# PWR_board_CHM.net
KiCad netlist of a schematic drawn in Altium Designer
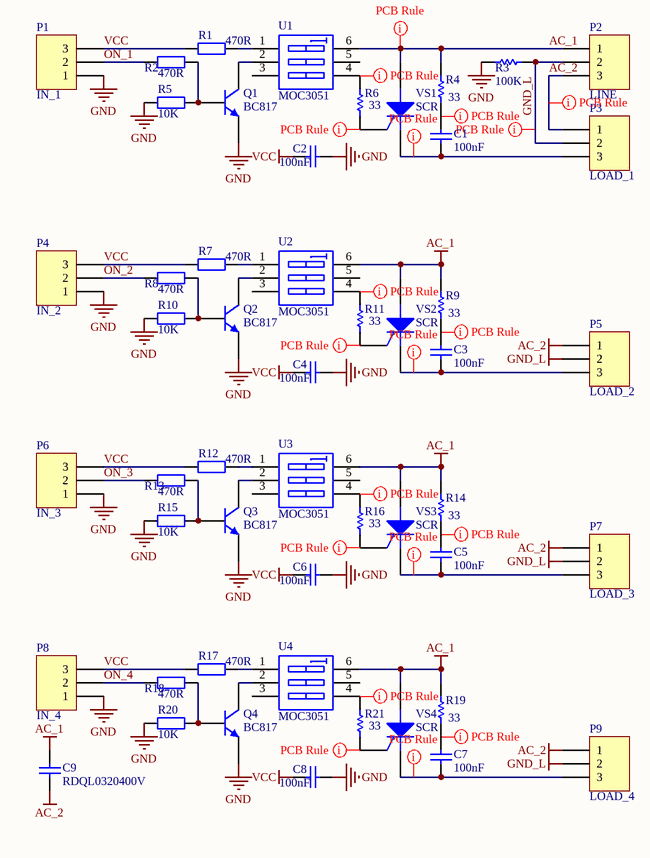
[diagram p0: PWR board_CHM.SchDoc]

(export (version "E")
  (design (tool "Eeschema 10.0.6"))
  (components
    (comp (ref "C1")
      (value "100nF")
      (footprint "AXIAL-0.7")
      (description "Ceramic High Voltage Disc Capacitor, Class 2: 2200pF 6kV K 2000")
      (fields (field (name "PUBLISHER") "Altium Limited"))
      (libsource (lib "Vishay Draloric Ceramic Disc Capacitor") (part "HFZ222MBFEJ0K"))
    )
    (comp (ref "C2")
      (value "100nF")
      (footprint "0805")
      (description "Ceramic Chip Capacitor - Standard")
      (fields (field (name "Comment") "C0805") (field (name "PUBLISHER") "Altium Limited"))
      (libsource (lib "KEMET Chip Capacitor") (part "C0805"))
    )
    (comp (ref "C3")
      (value "100nF")
      (footprint "AXIAL-0.7")
      (description "Ceramic High Voltage Disc Capacitor, Class 2: 2200pF 6kV K 2000")
      (fields (field (name "PUBLISHER") "Altium Limited"))
      (libsource (lib "Vishay Draloric Ceramic Disc Capacitor") (part "HFZ222MBFEJ0K"))
    )
    (comp (ref "C4")
      (value "100nF")
      (footprint "0805")
      (description "Ceramic Chip Capacitor - Standard")
      (fields (field (name "Comment") "C0805") (field (name "PUBLISHER") "Altium Limited"))
      (libsource (lib "KEMET Chip Capacitor") (part "C0805"))
    )
    (comp (ref "C5")
      (value "100nF")
      (footprint "AXIAL-0.7")
      (description "Ceramic High Voltage Disc Capacitor, Class 2: 2200pF 6kV K 2000")
      (fields (field (name "PUBLISHER") "Altium Limited"))
      (libsource (lib "Vishay Draloric Ceramic Disc Capacitor") (part "HFZ222MBFEJ0K"))
    )
    (comp (ref "C6")
      (value "100nF")
      (footprint "0805")
      (description "Ceramic Chip Capacitor - Standard")
      (fields (field (name "Comment") "C0805") (field (name "PUBLISHER") "Altium Limited"))
      (libsource (lib "KEMET Chip Capacitor") (part "C0805"))
    )
    (comp (ref "C7")
      (value "100nF")
      (footprint "AXIAL-0.7")
      (description "Ceramic High Voltage Disc Capacitor, Class 2: 2200pF 6kV K 2000")
      (fields (field (name "PUBLISHER") "Altium Limited"))
      (libsource (lib "Vishay Draloric Ceramic Disc Capacitor") (part "HFZ222MBFEJ0K"))
    )
    (comp (ref "C8")
      (value "100nF")
      (footprint "0805")
      (description "Ceramic Chip Capacitor - Standard")
      (fields (field (name "Comment") "C0805") (field (name "PUBLISHER") "Altium Limited"))
      (libsource (lib "KEMET Chip Capacitor") (part "C0805"))
    )
    (comp (ref "C9")
      (value "RDQL0320400V")
      (footprint "AXIAL-0.7")
      (fields (field (name "PUBLISHER") "Altium Limited"))
      (libsource (lib "Vishay Draloric Ceramic Tubular Capacitor") (part "RDQL0320400V"))
    )
    (comp (ref "P1")
      (value "IN_1")
      (footprint "DG390-5.0-03P")
      (description "Header, 3-Pin")
      (fields (field (name "PUBLISHER") "Altium Limited"))
      (libsource (lib "") (part "Header 3_1"))
    )
    (comp (ref "P2")
      (value "LINE")
      (footprint "DG390-5.0-03P")
      (description "Header, 3-Pin")
      (fields (field (name "PUBLISHER") "Altium Limited"))
      (libsource (lib "Miscellaneous Connectors") (part "Header 3"))
    )
    (comp (ref "P3")
      (value "LOAD_1")
      (footprint "DG390-5.0-03P")
      (description "Header, 3-Pin")
      (fields (field (name "PUBLISHER") "Altium Limited"))
      (libsource (lib "Miscellaneous Connectors") (part "Header 3"))
    )
    (comp (ref "P4")
      (value "IN_2")
      (footprint "DG390-5.0-03P")
      (description "Header, 3-Pin")
      (fields (field (name "PUBLISHER") "Altium Limited"))
      (libsource (lib "") (part "Header 3_1"))
    )
    (comp (ref "P5")
      (value "LOAD_2")
      (footprint "DG390-5.0-03P")
      (description "Header, 3-Pin")
      (fields (field (name "PUBLISHER") "Altium Limited"))
      (libsource (lib "Miscellaneous Connectors") (part "Header 3"))
    )
    (comp (ref "P6")
      (value "IN_3")
      (footprint "DG390-5.0-03P")
      (description "Header, 3-Pin")
      (fields (field (name "PUBLISHER") "Altium Limited"))
      (libsource (lib "") (part "Header 3_1"))
    )
    (comp (ref "P7")
      (value "LOAD_3")
      (footprint "DG390-5.0-03P")
      (description "Header, 3-Pin")
      (fields (field (name "PUBLISHER") "Altium Limited"))
      (libsource (lib "Miscellaneous Connectors") (part "Header 3"))
    )
    (comp (ref "P8")
      (value "IN_4")
      (footprint "DG390-5.0-03P")
      (description "Header, 3-Pin")
      (fields (field (name "PUBLISHER") "Altium Limited"))
      (libsource (lib "") (part "Header 3_1"))
    )
    (comp (ref "P9")
      (value "LOAD_4")
      (footprint "DG390-5.0-03P")
      (description "Header, 3-Pin")
      (fields (field (name "PUBLISHER") "Altium Limited"))
      (libsource (lib "Miscellaneous Connectors") (part "Header 3"))
    )
    (comp (ref "Q1")
      (value "BC817")
      (footprint "SOT23_M")
      (description "NPN Bipolar Transistor")
      (fields (field (name "PUBLISHER") "Altium Limited"))
      (libsource (lib "Miscellaneous Devices") (part "QNPN"))
    )
    (comp (ref "Q2")
      (value "BC817")
      (footprint "SOT23_M")
      (description "NPN Bipolar Transistor")
      (fields (field (name "PUBLISHER") "Altium Limited"))
      (libsource (lib "Miscellaneous Devices") (part "QNPN"))
    )
    (comp (ref "Q3")
      (value "BC817")
      (footprint "SOT23_M")
      (description "NPN Bipolar Transistor")
      (fields (field (name "PUBLISHER") "Altium Limited"))
      (libsource (lib "Miscellaneous Devices") (part "QNPN"))
    )
    (comp (ref "Q4")
      (value "BC817")
      (footprint "SOT23_M")
      (description "NPN Bipolar Transistor")
      (fields (field (name "PUBLISHER") "Altium Limited"))
      (libsource (lib "Miscellaneous Devices") (part "QNPN"))
    )
    (comp (ref "R1")
      (value "470R")
      (footprint "6-0805_N")
      (description "Resistor")
      (fields (field (name "Comment") "Res2") (field (name "PUBLISHER") "Altium Limited"))
      (libsource (lib "Miscellaneous Devices") (part "Res2"))
    )
    (comp (ref "R2")
      (value "470R")
      (footprint "6-0805_N")
      (description "Resistor")
      (fields (field (name "Comment") "Res2") (field (name "PUBLISHER") "Altium Limited"))
      (libsource (lib "") (part "Res2_1"))
    )
    (comp (ref "R3")
      (value "100K")
      (footprint "AXIAL-0.5")
      (description "Semiconductor Resistor")
      (fields (field (name "Comment") "Res Semi") (field (name "PUBLISHER") "Altium Limited"))
      (libsource (lib "Miscellaneous Devices") (part "Res Semi"))
    )
    (comp (ref "R4")
      (value "33")
      (footprint "AXIAL-0.5")
      (description "Semiconductor Resistor")
      (fields (field (name "Comment") "Res Semi") (field (name "PUBLISHER") "Altium Limited"))
      (libsource (lib "Miscellaneous Devices") (part "Res Semi"))
    )
    (comp (ref "R5")
      (value "10K")
      (footprint "6-0805_N")
      (description "Resistor")
      (fields (field (name "Comment") "Res2") (field (name "PUBLISHER") "Altium Limited"))
      (libsource (lib "Miscellaneous Devices") (part "Res2"))
    )
    (comp (ref "R6")
      (value "33")
      (footprint "AXIAL-0.5")
      (description "Semiconductor Resistor")
      (fields (field (name "Comment") "Res Semi") (field (name "PUBLISHER") "Altium Limited"))
      (libsource (lib "Miscellaneous Devices") (part "Res Semi"))
    )
    (comp (ref "R7")
      (value "470R")
      (footprint "6-0805_N")
      (description "Resistor")
      (fields (field (name "Comment") "Res2") (field (name "PUBLISHER") "Altium Limited"))
      (libsource (lib "Miscellaneous Devices") (part "Res2"))
    )
    (comp (ref "R8")
      (value "470R")
      (footprint "6-0805_N")
      (description "Resistor")
      (fields (field (name "Comment") "Res2") (field (name "PUBLISHER") "Altium Limited"))
      (libsource (lib "") (part "Res2_1"))
    )
    (comp (ref "R9")
      (value "33")
      (footprint "AXIAL-0.5")
      (description "Semiconductor Resistor")
      (fields (field (name "Comment") "Res Semi") (field (name "PUBLISHER") "Altium Limited"))
      (libsource (lib "Miscellaneous Devices") (part "Res Semi"))
    )
    (comp (ref "R10")
      (value "10K")
      (footprint "6-0805_N")
      (description "Resistor")
      (fields (field (name "Comment") "Res2") (field (name "PUBLISHER") "Altium Limited"))
      (libsource (lib "Miscellaneous Devices") (part "Res2"))
    )
    (comp (ref "R11")
      (value "33")
      (footprint "AXIAL-0.5")
      (description "Semiconductor Resistor")
      (fields (field (name "Comment") "Res Semi") (field (name "PUBLISHER") "Altium Limited"))
      (libsource (lib "Miscellaneous Devices") (part "Res Semi"))
    )
    (comp (ref "R12")
      (value "470R")
      (footprint "6-0805_N")
      (description "Resistor")
      (fields (field (name "Comment") "Res2") (field (name "PUBLISHER") "Altium Limited"))
      (libsource (lib "Miscellaneous Devices") (part "Res2"))
    )
    (comp (ref "R13")
      (value "470R")
      (footprint "6-0805_N")
      (description "Resistor")
      (fields (field (name "Comment") "Res2") (field (name "PUBLISHER") "Altium Limited"))
      (libsource (lib "") (part "Res2_1"))
    )
    (comp (ref "R14")
      (value "33")
      (footprint "AXIAL-0.5")
      (description "Semiconductor Resistor")
      (fields (field (name "Comment") "Res Semi") (field (name "PUBLISHER") "Altium Limited"))
      (libsource (lib "Miscellaneous Devices") (part "Res Semi"))
    )
    (comp (ref "R15")
      (value "10K")
      (footprint "6-0805_N")
      (description "Resistor")
      (fields (field (name "Comment") "Res2") (field (name "PUBLISHER") "Altium Limited"))
      (libsource (lib "Miscellaneous Devices") (part "Res2"))
    )
    (comp (ref "R16")
      (value "33")
      (footprint "AXIAL-0.5")
      (description "Semiconductor Resistor")
      (fields (field (name "Comment") "Res Semi") (field (name "PUBLISHER") "Altium Limited"))
      (libsource (lib "Miscellaneous Devices") (part "Res Semi"))
    )
    (comp (ref "R17")
      (value "470R")
      (footprint "6-0805_N")
      (description "Resistor")
      (fields (field (name "Comment") "Res2") (field (name "PUBLISHER") "Altium Limited"))
      (libsource (lib "Miscellaneous Devices") (part "Res2"))
    )
    (comp (ref "R18")
      (value "470R")
      (footprint "6-0805_N")
      (description "Resistor")
      (fields (field (name "Comment") "Res2") (field (name "PUBLISHER") "Altium Limited"))
      (libsource (lib "") (part "Res2_1"))
    )
    (comp (ref "R19")
      (value "33")
      (footprint "AXIAL-0.5")
      (description "Semiconductor Resistor")
      (fields (field (name "Comment") "Res Semi") (field (name "PUBLISHER") "Altium Limited"))
      (libsource (lib "Miscellaneous Devices") (part "Res Semi"))
    )
    (comp (ref "R20")
      (value "10K")
      (footprint "6-0805_N")
      (description "Resistor")
      (fields (field (name "Comment") "Res2") (field (name "PUBLISHER") "Altium Limited"))
      (libsource (lib "Miscellaneous Devices") (part "Res2"))
    )
    (comp (ref "R21")
      (value "33")
      (footprint "AXIAL-0.5")
      (description "Semiconductor Resistor")
      (fields (field (name "Comment") "Res Semi") (field (name "PUBLISHER") "Altium Limited"))
      (libsource (lib "Miscellaneous Devices") (part "Res Semi"))
    )
    (comp (ref "U1")
      (value "MOC3051")
      (footprint "DIP-6")
      (description "DIP Switch, 3 Position, SPST")
      (fields (field (name "PUBLISHER") "Altium Limited"))
      (libsource (lib "Miscellaneous Devices") (part "SW DIP-3"))
    )
    (comp (ref "U2")
      (value "MOC3051")
      (footprint "DIP-6")
      (description "DIP Switch, 3 Position, SPST")
      (fields (field (name "PUBLISHER") "Altium Limited"))
      (libsource (lib "Miscellaneous Devices") (part "SW DIP-3"))
    )
    (comp (ref "U3")
      (value "MOC3051")
      (footprint "DIP-6")
      (description "DIP Switch, 3 Position, SPST")
      (fields (field (name "PUBLISHER") "Altium Limited"))
      (libsource (lib "Miscellaneous Devices") (part "SW DIP-3"))
    )
    (comp (ref "U4")
      (value "MOC3051")
      (footprint "DIP-6")
      (description "DIP Switch, 3 Position, SPST")
      (fields (field (name "PUBLISHER") "Altium Limited"))
      (libsource (lib "Miscellaneous Devices") (part "SW DIP-3"))
    )
    (comp (ref "VS1")
      (value "SCR")
      (footprint "Super-TO-247AC")
      (description "Silicon Controlled Rectifier")
      (fields (field (name "PUBLISHER") "Altium Limited"))
      (libsource (lib "Miscellaneous Devices") (part "SCR"))
    )
    (comp (ref "VS2")
      (value "SCR")
      (footprint "Super-TO-247AC")
      (description "Silicon Controlled Rectifier")
      (fields (field (name "PUBLISHER") "Altium Limited"))
      (libsource (lib "Miscellaneous Devices") (part "SCR"))
    )
    (comp (ref "VS3")
      (value "SCR")
      (footprint "Super-TO-247AC")
      (description "Silicon Controlled Rectifier")
      (fields (field (name "PUBLISHER") "Altium Limited"))
      (libsource (lib "Miscellaneous Devices") (part "SCR"))
    )
    (comp (ref "VS4")
      (value "SCR")
      (footprint "Super-TO-247AC")
      (description "Silicon Controlled Rectifier")
      (fields (field (name "PUBLISHER") "Altium Limited"))
      (libsource (lib "Miscellaneous Devices") (part "SCR"))
    )
  )
  (nets
    (net (code "1") (name "/ON_1") (class "Default")
      (node (ref "P1") (pin "2") (pinfunction "2_2") (pintype "passive"))
      (node (ref "R2") (pin "2") (pinfunction "2_2") (pintype "passive"))
    )
    (net (code "2") (name "/ON_2") (class "Default")
      (node (ref "P4") (pin "2") (pinfunction "2_2") (pintype "passive"))
      (node (ref "R8") (pin "2") (pinfunction "2_2") (pintype "passive"))
    )
    (net (code "3") (name "/ON_3") (class "Default")
      (node (ref "P6") (pin "2") (pinfunction "2_2") (pintype "passive"))
      (node (ref "R13") (pin "2") (pinfunction "2_2") (pintype "passive"))
    )
    (net (code "4") (name "/ON_4") (class "Default")
      (node (ref "P8") (pin "2") (pinfunction "2_2") (pintype "passive"))
      (node (ref "R18") (pin "2") (pinfunction "2_2") (pintype "passive"))
    )
    (net (code "5") (name "AC_1") (class "Default")
      (node (ref "C9") (pin "2") (pinfunction "2_2") (pintype "passive"))
      (node (ref "P2") (pin "1") (pinfunction "1_1") (pintype "passive"))
      (node (ref "R14") (pin "2") (pinfunction "2_2") (pintype "passive"))
      (node (ref "R19") (pin "2") (pinfunction "2_2") (pintype "passive"))
      (node (ref "R4") (pin "2") (pinfunction "2_2") (pintype "passive"))
      (node (ref "R9") (pin "2") (pinfunction "2_2") (pintype "passive"))
      (node (ref "U1") (pin "6") (pinfunction "B1_6") (pintype "passive"))
      (node (ref "U2") (pin "6") (pinfunction "B1_6") (pintype "passive"))
      (node (ref "U3") (pin "6") (pinfunction "B1_6") (pintype "passive"))
      (node (ref "U4") (pin "6") (pinfunction "B1_6") (pintype "passive"))
      (node (ref "VS1") (pin "1") (pinfunction "A_1") (pintype "passive"))
      (node (ref "VS2") (pin "1") (pinfunction "A_1") (pintype "passive"))
      (node (ref "VS3") (pin "1") (pinfunction "A_1") (pintype "passive"))
      (node (ref "VS4") (pin "1") (pinfunction "A_1") (pintype "passive"))
    )
    (net (code "6") (name "AC_2") (class "Default")
      (node (ref "C9") (pin "1") (pinfunction "1_1") (pintype "passive"))
      (node (ref "P2") (pin "3") (pinfunction "3_3") (pintype "passive"))
      (node (ref "P3") (pin "1") (pinfunction "1_1") (pintype "passive"))
      (node (ref "P5") (pin "1") (pinfunction "1_1") (pintype "passive"))
      (node (ref "P7") (pin "1") (pinfunction "1_1") (pintype "passive"))
      (node (ref "P9") (pin "1") (pinfunction "1_1") (pintype "passive"))
    )
    (net (code "7") (name "GND") (class "Default")
      (node (ref "C2") (pin "2") (pinfunction "2_2") (pintype "passive"))
      (node (ref "C4") (pin "2") (pinfunction "2_2") (pintype "passive"))
      (node (ref "C6") (pin "2") (pinfunction "2_2") (pintype "passive"))
      (node (ref "C8") (pin "2") (pinfunction "2_2") (pintype "passive"))
      (node (ref "P1") (pin "1") (pinfunction "1_1") (pintype "passive"))
      (node (ref "P4") (pin "1") (pinfunction "1_1") (pintype "passive"))
      (node (ref "P6") (pin "1") (pinfunction "1_1") (pintype "passive"))
      (node (ref "P8") (pin "1") (pinfunction "1_1") (pintype "passive"))
      (node (ref "Q1") (pin "3") (pinfunction "E_3") (pintype "passive"))
      (node (ref "Q2") (pin "3") (pinfunction "E_3") (pintype "passive"))
      (node (ref "Q3") (pin "3") (pinfunction "E_3") (pintype "passive"))
      (node (ref "Q4") (pin "3") (pinfunction "E_3") (pintype "passive"))
      (node (ref "R10") (pin "1") (pinfunction "1_1") (pintype "passive"))
      (node (ref "R15") (pin "1") (pinfunction "1_1") (pintype "passive"))
      (node (ref "R20") (pin "1") (pinfunction "1_1") (pintype "passive"))
      (node (ref "R3") (pin "2") (pinfunction "2_2") (pintype "passive"))
      (node (ref "R5") (pin "1") (pinfunction "1_1") (pintype "passive"))
    )
    (net (code "8") (name "GND_L") (class "Default")
      (node (ref "P2") (pin "2") (pinfunction "2_2") (pintype "passive"))
      (node (ref "P3") (pin "2") (pinfunction "2_2") (pintype "passive"))
      (node (ref "P5") (pin "2") (pinfunction "2_2") (pintype "passive"))
      (node (ref "P7") (pin "2") (pinfunction "2_2") (pintype "passive"))
      (node (ref "P9") (pin "2") (pinfunction "2_2") (pintype "passive"))
      (node (ref "R3") (pin "1") (pinfunction "1_1") (pintype "passive"))
    )
    (net (code "9") (name "Net-(C1-Pad2)") (class "Default")
      (node (ref "C1") (pin "2") (pinfunction "2_2") (pintype "passive"))
      (node (ref "R4") (pin "1") (pinfunction "1_1") (pintype "passive"))
    )
    (net (code "10") (name "Net-(C3-Pad2)") (class "Default")
      (node (ref "C3") (pin "2") (pinfunction "2_2") (pintype "passive"))
      (node (ref "R9") (pin "1") (pinfunction "1_1") (pintype "passive"))
    )
    (net (code "11") (name "Net-(C5-Pad2)") (class "Default")
      (node (ref "C5") (pin "2") (pinfunction "2_2") (pintype "passive"))
      (node (ref "R14") (pin "1") (pinfunction "1_1") (pintype "passive"))
    )
    (net (code "12") (name "Net-(C7-Pad2)") (class "Default")
      (node (ref "C7") (pin "2") (pinfunction "2_2") (pintype "passive"))
      (node (ref "R19") (pin "1") (pinfunction "1_1") (pintype "passive"))
    )
    (net (code "13") (name "Net-(Q1-B)") (class "Default")
      (node (ref "Q1") (pin "2") (pinfunction "B_2") (pintype "passive"))
      (node (ref "R2") (pin "1") (pinfunction "1_1") (pintype "passive"))
      (node (ref "R5") (pin "2") (pinfunction "2_2") (pintype "passive"))
    )
    (net (code "14") (name "Net-(Q1-C)") (class "Default")
      (node (ref "Q1") (pin "1") (pinfunction "C_1") (pintype "passive"))
      (node (ref "U1") (pin "2") (pinfunction "A2_2") (pintype "passive"))
    )
    (net (code "15") (name "Net-(Q2-B)") (class "Default")
      (node (ref "Q2") (pin "2") (pinfunction "B_2") (pintype "passive"))
      (node (ref "R10") (pin "2") (pinfunction "2_2") (pintype "passive"))
      (node (ref "R8") (pin "1") (pinfunction "1_1") (pintype "passive"))
    )
    (net (code "16") (name "Net-(Q2-C)") (class "Default")
      (node (ref "Q2") (pin "1") (pinfunction "C_1") (pintype "passive"))
      (node (ref "U2") (pin "2") (pinfunction "A2_2") (pintype "passive"))
    )
    (net (code "17") (name "Net-(Q3-B)") (class "Default")
      (node (ref "Q3") (pin "2") (pinfunction "B_2") (pintype "passive"))
      (node (ref "R13") (pin "1") (pinfunction "1_1") (pintype "passive"))
      (node (ref "R15") (pin "2") (pinfunction "2_2") (pintype "passive"))
    )
    (net (code "18") (name "Net-(Q3-C)") (class "Default")
      (node (ref "Q3") (pin "1") (pinfunction "C_1") (pintype "passive"))
      (node (ref "U3") (pin "2") (pinfunction "A2_2") (pintype "passive"))
    )
    (net (code "19") (name "Net-(Q4-B)") (class "Default")
      (node (ref "Q4") (pin "2") (pinfunction "B_2") (pintype "passive"))
      (node (ref "R18") (pin "1") (pinfunction "1_1") (pintype "passive"))
      (node (ref "R20") (pin "2") (pinfunction "2_2") (pintype "passive"))
    )
    (net (code "20") (name "Net-(Q4-C)") (class "Default")
      (node (ref "Q4") (pin "1") (pinfunction "C_1") (pintype "passive"))
      (node (ref "U4") (pin "2") (pinfunction "A2_2") (pintype "passive"))
    )
    (net (code "21") (name "Net-(U1-A1)") (class "Default")
      (node (ref "R1") (pin "2") (pinfunction "2_2") (pintype "passive"))
      (node (ref "U1") (pin "1") (pinfunction "A1_1") (pintype "passive"))
    )
    (net (code "22") (name "Net-(U1-B3)") (class "Default")
      (node (ref "R6") (pin "2") (pinfunction "2_2") (pintype "passive"))
      (node (ref "U1") (pin "4") (pinfunction "B3_4") (pintype "passive"))
    )
    (net (code "23") (name "Net-(U2-A1)") (class "Default")
      (node (ref "R7") (pin "2") (pinfunction "2_2") (pintype "passive"))
      (node (ref "U2") (pin "1") (pinfunction "A1_1") (pintype "passive"))
    )
    (net (code "24") (name "Net-(U2-B3)") (class "Default")
      (node (ref "R11") (pin "2") (pinfunction "2_2") (pintype "passive"))
      (node (ref "U2") (pin "4") (pinfunction "B3_4") (pintype "passive"))
    )
    (net (code "25") (name "Net-(U3-A1)") (class "Default")
      (node (ref "R12") (pin "2") (pinfunction "2_2") (pintype "passive"))
      (node (ref "U3") (pin "1") (pinfunction "A1_1") (pintype "passive"))
    )
    (net (code "26") (name "Net-(U3-B3)") (class "Default")
      (node (ref "R16") (pin "2") (pinfunction "2_2") (pintype "passive"))
      (node (ref "U3") (pin "4") (pinfunction "B3_4") (pintype "passive"))
    )
    (net (code "27") (name "Net-(U4-A1)") (class "Default")
      (node (ref "R17") (pin "2") (pinfunction "2_2") (pintype "passive"))
      (node (ref "U4") (pin "1") (pinfunction "A1_1") (pintype "passive"))
    )
    (net (code "28") (name "Net-(U4-B3)") (class "Default")
      (node (ref "R21") (pin "2") (pinfunction "2_2") (pintype "passive"))
      (node (ref "U4") (pin "4") (pinfunction "B3_4") (pintype "passive"))
    )
    (net (code "29") (name "Net-(VS1-G)") (class "Default")
      (node (ref "R6") (pin "1") (pinfunction "1_1") (pintype "passive"))
      (node (ref "VS1") (pin "2") (pinfunction "G_2") (pintype "passive"))
    )
    (net (code "30") (name "Net-(VS1-K)") (class "Default")
      (node (ref "C1") (pin "1") (pinfunction "1_1") (pintype "passive"))
      (node (ref "P3") (pin "3") (pinfunction "3_3") (pintype "passive"))
      (node (ref "VS1") (pin "3") (pinfunction "K_3") (pintype "passive"))
    )
    (net (code "31") (name "Net-(VS2-G)") (class "Default")
      (node (ref "R11") (pin "1") (pinfunction "1_1") (pintype "passive"))
      (node (ref "VS2") (pin "2") (pinfunction "G_2") (pintype "passive"))
    )
    (net (code "32") (name "Net-(VS2-K)") (class "Default")
      (node (ref "C3") (pin "1") (pinfunction "1_1") (pintype "passive"))
      (node (ref "P5") (pin "3") (pinfunction "3_3") (pintype "passive"))
      (node (ref "VS2") (pin "3") (pinfunction "K_3") (pintype "passive"))
    )
    (net (code "33") (name "Net-(VS3-G)") (class "Default")
      (node (ref "R16") (pin "1") (pinfunction "1_1") (pintype "passive"))
      (node (ref "VS3") (pin "2") (pinfunction "G_2") (pintype "passive"))
    )
    (net (code "34") (name "Net-(VS3-K)") (class "Default")
      (node (ref "C5") (pin "1") (pinfunction "1_1") (pintype "passive"))
      (node (ref "P7") (pin "3") (pinfunction "3_3") (pintype "passive"))
      (node (ref "VS3") (pin "3") (pinfunction "K_3") (pintype "passive"))
    )
    (net (code "35") (name "Net-(VS4-G)") (class "Default")
      (node (ref "R21") (pin "1") (pinfunction "1_1") (pintype "passive"))
      (node (ref "VS4") (pin "2") (pinfunction "G_2") (pintype "passive"))
    )
    (net (code "36") (name "Net-(VS4-K)") (class "Default")
      (node (ref "C7") (pin "1") (pinfunction "1_1") (pintype "passive"))
      (node (ref "P9") (pin "3") (pinfunction "3_3") (pintype "passive"))
      (node (ref "VS4") (pin "3") (pinfunction "K_3") (pintype "passive"))
    )
    (net (code "37") (name "VCC") (class "Default")
      (node (ref "C2") (pin "1") (pinfunction "1_1") (pintype "passive"))
      (node (ref "C4") (pin "1") (pinfunction "1_1") (pintype "passive"))
      (node (ref "C6") (pin "1") (pinfunction "1_1") (pintype "passive"))
      (node (ref "C8") (pin "1") (pinfunction "1_1") (pintype "passive"))
      (node (ref "P1") (pin "3") (pinfunction "3_3") (pintype "passive"))
      (node (ref "P4") (pin "3") (pinfunction "3_3") (pintype "passive"))
      (node (ref "P6") (pin "3") (pinfunction "3_3") (pintype "passive"))
      (node (ref "P8") (pin "3") (pinfunction "3_3") (pintype "passive"))
      (node (ref "R1") (pin "1") (pinfunction "1_1") (pintype "passive"))
      (node (ref "R12") (pin "1") (pinfunction "1_1") (pintype "passive"))
      (node (ref "R17") (pin "1") (pinfunction "1_1") (pintype "passive"))
      (node (ref "R7") (pin "1") (pinfunction "1_1") (pintype "passive"))
    )
    (net (code "38") (name "unconnected-(U1-A3-Pad3)") (class "Default")
      (node (ref "U1") (pin "3") (pinfunction "A3_3") (pintype "passive"))
    )
    (net (code "39") (name "unconnected-(U1-B2-Pad5)") (class "Default")
      (node (ref "U1") (pin "5") (pinfunction "B2_5") (pintype "passive"))
    )
    (net (code "40") (name "unconnected-(U2-A3-Pad3)") (class "Default")
      (node (ref "U2") (pin "3") (pinfunction "A3_3") (pintype "passive"))
    )
    (net (code "41") (name "unconnected-(U2-B2-Pad5)") (class "Default")
      (node (ref "U2") (pin "5") (pinfunction "B2_5") (pintype "passive"))
    )
    (net (code "42") (name "unconnected-(U3-A3-Pad3)") (class "Default")
      (node (ref "U3") (pin "3") (pinfunction "A3_3") (pintype "passive"))
    )
    (net (code "43") (name "unconnected-(U3-B2-Pad5)") (class "Default")
      (node (ref "U3") (pin "5") (pinfunction "B2_5") (pintype "passive"))
    )
    (net (code "44") (name "unconnected-(U4-A3-Pad3)") (class "Default")
      (node (ref "U4") (pin "3") (pinfunction "A3_3") (pintype "passive"))
    )
    (net (code "45") (name "unconnected-(U4-B2-Pad5)") (class "Default")
      (node (ref "U4") (pin "5") (pinfunction "B2_5") (pintype "passive"))
    )
  )
)
